# FAT42.net
KiCad netlist of a schematic drawn in Altium Designer
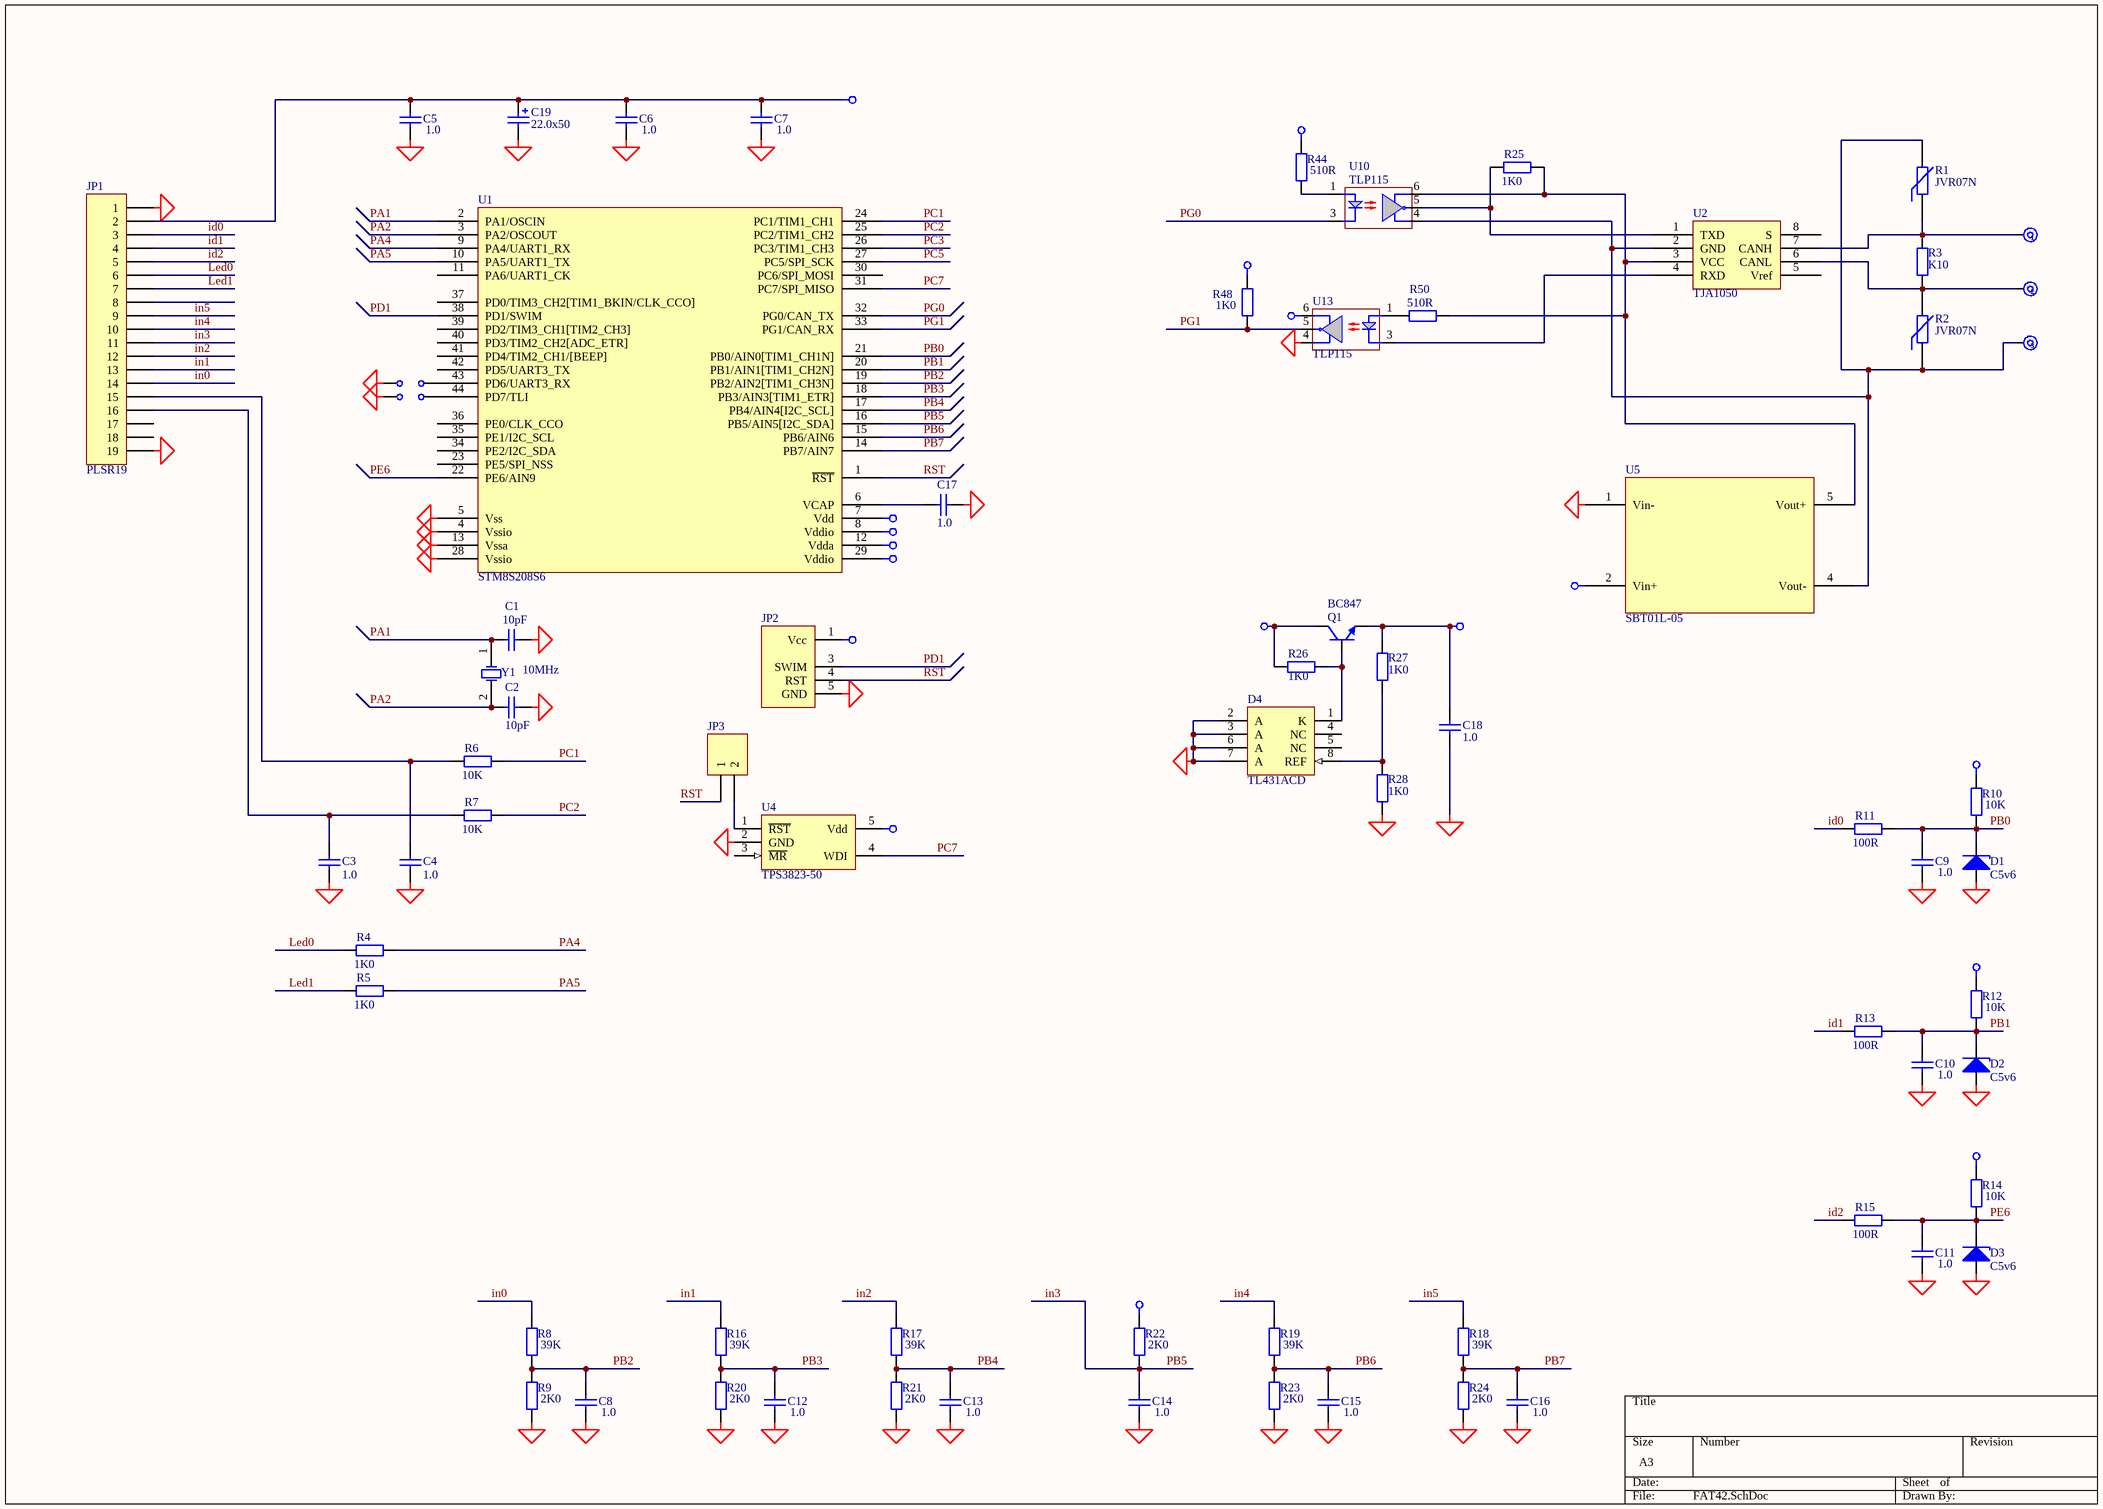
[diagram p0: FAT42.SchDoc]

(export (version "E")
  (design (tool "Eeschema 10.0.6"))
  (components
    (comp (ref "1")
      (value "~")
      (footprint "PIN2R")
      (description "Socket")
      (fields (field (name "MANUFACTURER") "Generic Components") (field (name "PUBLISHER") "Altium Limited"))
      (libsource (lib "PAL") (part "Socket_Ring"))
    )
    (comp (ref "2")
      (value "~")
      (footprint "PIN2R")
      (description "Socket")
      (fields (field (name "MANUFACTURER") "Generic Components") (field (name "PUBLISHER") "Altium Limited"))
      (libsource (lib "PAL") (part "Socket_Ring"))
    )
    (comp (ref "3")
      (value "~")
      (footprint "PIN2R")
      (description "Socket")
      (fields (field (name "MANUFACTURER") "Generic Components") (field (name "PUBLISHER") "Altium Limited"))
      (libsource (lib "PAL") (part "Socket_Ring"))
    )
    (comp (ref "C1")
      (value "10pF")
      (footprint "_1206")
      (description "Capacitor (Semiconductor SIM Model)")
      (fields (field (name "MANUFACTURER") "Generic Components") (field (name "PUBLISHER") "Altium Limited"))
      (libsource (lib "Miscellaneous Devices") (part "Cap Semi"))
    )
    (comp (ref "C2")
      (value "10pF")
      (footprint "_1206")
      (description "Capacitor (Semiconductor SIM Model)")
      (fields (field (name "MANUFACTURER") "Generic Components") (field (name "PUBLISHER") "Altium Limited"))
      (libsource (lib "Miscellaneous Devices") (part "Cap Semi"))
    )
    (comp (ref "C3")
      (value "1.0")
      (footprint "_1206")
      (description "Capacitor (Semiconductor SIM Model)")
      (fields (field (name "MANUFACTURER") "Generic Components") (field (name "PUBLISHER") "Altium Limited"))
      (libsource (lib "Miscellaneous Devices") (part "Cap Semi"))
    )
    (comp (ref "C4")
      (value "1.0")
      (footprint "_1206")
      (description "Capacitor (Semiconductor SIM Model)")
      (fields (field (name "MANUFACTURER") "Generic Components") (field (name "PUBLISHER") "Altium Limited"))
      (libsource (lib "Miscellaneous Devices") (part "Cap Semi"))
    )
    (comp (ref "C5")
      (value "1.0")
      (footprint "_1206")
      (description "Capacitor (Semiconductor SIM Model)")
      (fields (field (name "MANUFACTURER") "Generic Components") (field (name "PUBLISHER") "Altium Limited"))
      (libsource (lib "Miscellaneous Devices") (part "Cap Semi"))
    )
    (comp (ref "C6")
      (value "1.0")
      (footprint "_1206")
      (description "Capacitor (Semiconductor SIM Model)")
      (fields (field (name "MANUFACTURER") "Generic Components") (field (name "PUBLISHER") "Altium Limited"))
      (libsource (lib "Miscellaneous Devices") (part "Cap Semi"))
    )
    (comp (ref "C7")
      (value "1.0")
      (footprint "_1206")
      (description "Capacitor (Semiconductor SIM Model)")
      (fields (field (name "MANUFACTURER") "Generic Components") (field (name "PUBLISHER") "Altium Limited"))
      (libsource (lib "Miscellaneous Devices") (part "Cap Semi"))
    )
    (comp (ref "C8")
      (value "1.0")
      (footprint "_1206")
      (description "Capacitor (Semiconductor SIM Model)")
      (fields (field (name "MANUFACTURER") "Generic Components") (field (name "PUBLISHER") "Altium Limited"))
      (libsource (lib "Miscellaneous Devices") (part "Cap Semi"))
    )
    (comp (ref "C9")
      (value "1.0")
      (footprint "_1206")
      (description "Capacitor (Semiconductor SIM Model)")
      (fields (field (name "MANUFACTURER") "Generic Components") (field (name "PUBLISHER") "Altium Limited"))
      (libsource (lib "Miscellaneous Devices") (part "Cap Semi"))
    )
    (comp (ref "C10")
      (value "1.0")
      (footprint "_1206")
      (description "Capacitor (Semiconductor SIM Model)")
      (fields (field (name "MANUFACTURER") "Generic Components") (field (name "PUBLISHER") "Altium Limited"))
      (libsource (lib "Miscellaneous Devices") (part "Cap Semi"))
    )
    (comp (ref "C11")
      (value "1.0")
      (footprint "_1206")
      (description "Capacitor (Semiconductor SIM Model)")
      (fields (field (name "MANUFACTURER") "Generic Components") (field (name "PUBLISHER") "Altium Limited"))
      (libsource (lib "Miscellaneous Devices") (part "Cap Semi"))
    )
    (comp (ref "C12")
      (value "1.0")
      (footprint "_1206")
      (description "Capacitor (Semiconductor SIM Model)")
      (fields (field (name "MANUFACTURER") "Generic Components") (field (name "PUBLISHER") "Altium Limited"))
      (libsource (lib "Miscellaneous Devices") (part "Cap Semi"))
    )
    (comp (ref "C13")
      (value "1.0")
      (footprint "_1206")
      (description "Capacitor (Semiconductor SIM Model)")
      (fields (field (name "MANUFACTURER") "Generic Components") (field (name "PUBLISHER") "Altium Limited"))
      (libsource (lib "Miscellaneous Devices") (part "Cap Semi"))
    )
    (comp (ref "C14")
      (value "1.0")
      (footprint "_1206")
      (description "Capacitor (Semiconductor SIM Model)")
      (fields (field (name "MANUFACTURER") "Generic Components") (field (name "PUBLISHER") "Altium Limited"))
      (libsource (lib "Miscellaneous Devices") (part "Cap Semi"))
    )
    (comp (ref "C15")
      (value "1.0")
      (footprint "_1206")
      (description "Capacitor (Semiconductor SIM Model)")
      (fields (field (name "MANUFACTURER") "Generic Components") (field (name "PUBLISHER") "Altium Limited"))
      (libsource (lib "Miscellaneous Devices") (part "Cap Semi"))
    )
    (comp (ref "C16")
      (value "1.0")
      (footprint "_1206")
      (description "Capacitor (Semiconductor SIM Model)")
      (fields (field (name "MANUFACTURER") "Generic Components") (field (name "PUBLISHER") "Altium Limited"))
      (libsource (lib "Miscellaneous Devices") (part "Cap Semi"))
    )
    (comp (ref "C17")
      (value "1.0")
      (footprint "_1206")
      (description "Capacitor (Semiconductor SIM Model)")
      (fields (field (name "MANUFACTURER") "Generic Components") (field (name "PUBLISHER") "Altium Limited"))
      (libsource (lib "Miscellaneous Devices") (part "Cap Semi"))
    )
    (comp (ref "C18")
      (value "1.0")
      (footprint "_1206")
      (description "Capacitor (Semiconductor SIM Model)")
      (fields (field (name "MANUFACTURER") "Generic Components") (field (name "PUBLISHER") "Altium Limited"))
      (libsource (lib "Miscellaneous Devices") (part "Cap Semi"))
    )
    (comp (ref "C19")
      (value "22.0x50")
      (footprint "el3")
      (description "Polarized Capacitor (Radial)")
      (fields (field (name "MANUFACTURER") "Generic Components") (field (name "PUBLISHER") "Altium Limited"))
      (libsource (lib "PAL") (part "Cap Pol1"))
    )
    (comp (ref "D1")
      (value "C5v6")
      (footprint "_1206d")
      (description "Default Diode")
      (fields (field (name "MANUFACTURER") "Generic Components") (field (name "PUBLISHER") "Altium Limited"))
      (libsource (lib "PAL") (part "Zener"))
    )
    (comp (ref "D2")
      (value "C5v6")
      (footprint "_1206d")
      (description "Default Diode")
      (fields (field (name "MANUFACTURER") "Generic Components") (field (name "PUBLISHER") "Altium Limited"))
      (libsource (lib "PAL") (part "Zener"))
    )
    (comp (ref "D3")
      (value "C5v6")
      (footprint "_1206d")
      (description "Default Diode")
      (fields (field (name "MANUFACTURER") "Generic Components") (field (name "PUBLISHER") "Altium Limited"))
      (libsource (lib "PAL") (part "Zener"))
    )
    (comp (ref "D4")
      (value "TL431ACD")
      (footprint "SO-G8")
      (description "Programmable Precision Reference")
      (fields (field (name "MANUFACTURER") "Motorola") (field (name "PUBLISHER") "Altium Limited"))
      (libsource (lib "Motorola Power Management Voltage Reference") (part "TL431ACD"))
    )
    (comp (ref "J1")
      (value "~")
      (footprint "jmp")
      (description "Switch")
      (fields (field (name "MANUFACTURER") "Generic Components") (field (name "PUBLISHER") "Altium Limited"))
      (libsource (lib "PAL") (part "JMP"))
    )
    (comp (ref "J2")
      (value "~")
      (footprint "jmp")
      (description "Switch")
      (fields (field (name "MANUFACTURER") "Generic Components") (field (name "PUBLISHER") "Altium Limited"))
      (libsource (lib "PAL") (part "JMP"))
    )
    (comp (ref "JP1")
      (value "PLSR19")
      (footprint "HDR1X19")
      (description "Header, 19-Pin")
      (fields (field (name "MANUFACTURER") "Generic Components") (field (name "PUBLISHER") "Altium Limited"))
      (libsource (lib "Miscellaneous Connectors") (part "Header 19"))
    )
    (comp (ref "JP2") (value "~") (footprint "HDR1X5_uart") (libsource (lib "PAL") (part "SWIM_CONN")))
    (comp (ref "JP3")
      (value "PLS2")
      (footprint "HDR1X2")
      (description "Header, 2-Pin")
      (fields (field (name "MANUFACTURER") "Generic Components") (field (name "PUBLISHER") "Altium Limited"))
      (libsource (lib "Miscellaneous Connectors") (part "Header 2"))
    )
    (comp (ref "Q1")
      (value "BC847")
      (footprint "SO-G3")
      (description "General Purpose Transistor NPN Silicon")
      (fields (field (name "MANUFACTURER") "Motorola") (field (name "PUBLISHER") "Altium Limited"))
      (libsource (lib "PAL") (part "BC847ALT1"))
    )
    (comp (ref "R1")
      (value "JVR07N")
      (footprint "JVR07N")
      (description "Varistor (Voltage-Sensitive Resistor)")
      (fields (field (name "MANUFACTURER") "Generic Components") (field (name "PUBLISHER") "Altium Limited"))
      (libsource (lib "Miscellaneous Devices") (part "Res Varistor"))
    )
    (comp (ref "R2")
      (value "JVR07N")
      (footprint "JVR07N")
      (description "Varistor (Voltage-Sensitive Resistor)")
      (fields (field (name "MANUFACTURER") "Generic Components") (field (name "PUBLISHER") "Altium Limited"))
      (libsource (lib "Miscellaneous Devices") (part "Res Varistor"))
    )
    (comp (ref "R3")
      (value "K10")
      (footprint "_1206")
      (description "Resistor")
      (fields (field (name "MANUFACTURER") "Generic Components") (field (name "PUBLISHER") "Altium Limited"))
      (libsource (lib "") (part "Res2_3"))
    )
    (comp (ref "R4")
      (value "1K0")
      (footprint "_1206")
      (description "Resistor")
      (fields (field (name "MANUFACTURER") "Generic Components") (field (name "PUBLISHER") "Altium Limited"))
      (libsource (lib "") (part "Res2_3"))
    )
    (comp (ref "R5")
      (value "1K0")
      (footprint "_1206")
      (description "Resistor")
      (fields (field (name "MANUFACTURER") "Generic Components") (field (name "PUBLISHER") "Altium Limited"))
      (libsource (lib "") (part "Res2_3"))
    )
    (comp (ref "R6")
      (value "10K")
      (footprint "_1206")
      (description "Resistor")
      (fields (field (name "MANUFACTURER") "Generic Components") (field (name "PUBLISHER") "Altium Limited"))
      (libsource (lib "") (part "Res2_2"))
    )
    (comp (ref "R7")
      (value "10K")
      (footprint "_1206")
      (description "Resistor")
      (fields (field (name "MANUFACTURER") "Generic Components") (field (name "PUBLISHER") "Altium Limited"))
      (libsource (lib "") (part "Res2_2"))
    )
    (comp (ref "R8")
      (value "39K")
      (footprint "_1206")
      (description "Resistor")
      (fields (field (name "MANUFACTURER") "Generic Components") (field (name "PUBLISHER") "Altium Limited"))
      (libsource (lib "Miscellaneous Devices") (part "Res2"))
    )
    (comp (ref "R9")
      (value "2K0")
      (footprint "_1206")
      (description "Resistor")
      (fields (field (name "MANUFACTURER") "Generic Components") (field (name "PUBLISHER") "Altium Limited"))
      (libsource (lib "Miscellaneous Devices") (part "Res2"))
    )
    (comp (ref "R10")
      (value "10K")
      (footprint "_1206")
      (description "Resistor")
      (fields (field (name "MANUFACTURER") "Generic Components") (field (name "PUBLISHER") "Altium Limited"))
      (libsource (lib "") (part "Res2_1"))
    )
    (comp (ref "R11")
      (value "100R")
      (footprint "_1206")
      (description "Resistor")
      (fields (field (name "MANUFACTURER") "Generic Components") (field (name "PUBLISHER") "Altium Limited"))
      (libsource (lib "") (part "Res2_2"))
    )
    (comp (ref "R12")
      (value "10K")
      (footprint "_1206")
      (description "Resistor")
      (fields (field (name "MANUFACTURER") "Generic Components") (field (name "PUBLISHER") "Altium Limited"))
      (libsource (lib "") (part "Res2_1"))
    )
    (comp (ref "R13")
      (value "100R")
      (footprint "_1206")
      (description "Resistor")
      (fields (field (name "MANUFACTURER") "Generic Components") (field (name "PUBLISHER") "Altium Limited"))
      (libsource (lib "") (part "Res2_2"))
    )
    (comp (ref "R14")
      (value "10K")
      (footprint "_1206")
      (description "Resistor")
      (fields (field (name "MANUFACTURER") "Generic Components") (field (name "PUBLISHER") "Altium Limited"))
      (libsource (lib "") (part "Res2_1"))
    )
    (comp (ref "R15")
      (value "100R")
      (footprint "_1206")
      (description "Resistor")
      (fields (field (name "MANUFACTURER") "Generic Components") (field (name "PUBLISHER") "Altium Limited"))
      (libsource (lib "") (part "Res2_2"))
    )
    (comp (ref "R16")
      (value "39K")
      (footprint "_1206")
      (description "Resistor")
      (fields (field (name "MANUFACTURER") "Generic Components") (field (name "PUBLISHER") "Altium Limited"))
      (libsource (lib "Miscellaneous Devices") (part "Res2"))
    )
    (comp (ref "R17")
      (value "39K")
      (footprint "_1206")
      (description "Resistor")
      (fields (field (name "MANUFACTURER") "Generic Components") (field (name "PUBLISHER") "Altium Limited"))
      (libsource (lib "Miscellaneous Devices") (part "Res2"))
    )
    (comp (ref "R18")
      (value "39K")
      (footprint "_1206")
      (description "Resistor")
      (fields (field (name "MANUFACTURER") "Generic Components") (field (name "PUBLISHER") "Altium Limited"))
      (libsource (lib "Miscellaneous Devices") (part "Res2"))
    )
    (comp (ref "R19")
      (value "39K")
      (footprint "_1206")
      (description "Resistor")
      (fields (field (name "MANUFACTURER") "Generic Components") (field (name "PUBLISHER") "Altium Limited"))
      (libsource (lib "Miscellaneous Devices") (part "Res2"))
    )
    (comp (ref "R20")
      (value "2K0")
      (footprint "_1206")
      (description "Resistor")
      (fields (field (name "MANUFACTURER") "Generic Components") (field (name "PUBLISHER") "Altium Limited"))
      (libsource (lib "Miscellaneous Devices") (part "Res2"))
    )
    (comp (ref "R21")
      (value "2K0")
      (footprint "_1206")
      (description "Resistor")
      (fields (field (name "MANUFACTURER") "Generic Components") (field (name "PUBLISHER") "Altium Limited"))
      (libsource (lib "Miscellaneous Devices") (part "Res2"))
    )
    (comp (ref "R22")
      (value "2K0")
      (footprint "_1206")
      (description "Resistor")
      (fields (field (name "MANUFACTURER") "Generic Components") (field (name "PUBLISHER") "Altium Limited"))
      (libsource (lib "Miscellaneous Devices") (part "Res2"))
    )
    (comp (ref "R23")
      (value "2K0")
      (footprint "_1206")
      (description "Resistor")
      (fields (field (name "MANUFACTURER") "Generic Components") (field (name "PUBLISHER") "Altium Limited"))
      (libsource (lib "Miscellaneous Devices") (part "Res2"))
    )
    (comp (ref "R24")
      (value "2K0")
      (footprint "_1206")
      (description "Resistor")
      (fields (field (name "MANUFACTURER") "Generic Components") (field (name "PUBLISHER") "Altium Limited"))
      (libsource (lib "Miscellaneous Devices") (part "Res2"))
    )
    (comp (ref "R25")
      (value "1K0")
      (footprint "_1206")
      (description "Resistor")
      (fields (field (name "MANUFACTURER") "Generic Components") (field (name "PUBLISHER") "Altium Limited"))
      (libsource (lib "") (part "Res2_5"))
    )
    (comp (ref "R26")
      (value "1K0")
      (footprint "_1206")
      (description "Resistor")
      (fields (field (name "MANUFACTURER") "Generic Components") (field (name "PUBLISHER") "Altium Limited"))
      (libsource (lib "") (part "Res2_5"))
    )
    (comp (ref "R27")
      (value "1K0")
      (footprint "_1206")
      (description "Resistor")
      (fields (field (name "MANUFACTURER") "Generic Components") (field (name "PUBLISHER") "Altium Limited"))
      (libsource (lib "") (part "Res2_3"))
    )
    (comp (ref "R28")
      (value "1K0")
      (footprint "_1206")
      (description "Resistor")
      (fields (field (name "MANUFACTURER") "Generic Components") (field (name "PUBLISHER") "Altium Limited"))
      (libsource (lib "") (part "Res2_3"))
    )
    (comp (ref "R44")
      (value "510R")
      (footprint "_1206")
      (description "Resistor")
      (fields (field (name "MANUFACTURER") "Generic Components") (field (name "PUBLISHER") "Altium Limited"))
      (libsource (lib "") (part "Res2_3"))
    )
    (comp (ref "R48")
      (value "1K0")
      (footprint "_1206")
      (description "Resistor")
      (fields (field (name "MANUFACTURER") "Generic Components") (field (name "PUBLISHER") "Altium Limited"))
      (libsource (lib "") (part "Res2_3"))
    )
    (comp (ref "R50")
      (value "510R")
      (footprint "_1206")
      (description "Resistor")
      (fields (field (name "MANUFACTURER") "Generic Components") (field (name "PUBLISHER") "Altium Limited"))
      (libsource (lib "") (part "Res2_4"))
    )
    (comp (ref "U1")
      (value "STM8S208S6")
      (footprint "QFP10X10-G44/G10N")
      (libsource (lib "PAL") (part "STM8S208S6"))
    )
    (comp (ref "U2") (value "TJA1050") (footprint "SO-G8/D5") (libsource (lib "PAL") (part "TJA1050")))
    (comp (ref "U4")
      (value "TPS3823-50")
      (footprint "SO-G5/P.95")
      (description "Reset IC")
      (fields
        (field (name "MANUFACTURER") "National Semiconductor")
        (field (name "PUBLISHER") "Altium Limited")
      )
      (libsource (lib "PAL") (part "TPS3823"))
    )
    (comp (ref "U5") (value "SBT01L-05") (footprint "SBT01DET01") (libsource (lib "PAL") (part "SBT01L")))
    (comp (ref "U10") (value "TLP115") (footprint "tlp115") (libsource (lib "") (part "TLP115_1")))
    (comp (ref "U13") (value "TLP115") (footprint "tlp115") (libsource (lib "PAL") (part "TLP115")))
    (comp (ref "Y1")
      (value "10MHz")
      (footprint "QWARZ1")
      (description "Crystal Oscillator")
      (fields (field (name "MANUFACTURER") "Generic Components") (field (name "PUBLISHER") "Altium Limited"))
      (libsource (lib "Miscellaneous Devices") (part "XTAL"))
    )
  )
  (nets
    (net (code "1") (name "+5v") (class "Default")
      (node (ref "C19") (pin "1") (pinfunction "1_1") (pintype "passive"))
      (node (ref "C5") (pin "2") (pinfunction "2_2") (pintype "passive"))
      (node (ref "C6") (pin "2") (pinfunction "2_2") (pintype "passive"))
      (node (ref "C7") (pin "2") (pinfunction "2_2") (pintype "passive"))
      (node (ref "JP1") (pin "2") (pinfunction "2_2") (pintype "passive"))
      (node (ref "JP2") (pin "1") (pinfunction "Vcc_1") (pintype "passive"))
      (node (ref "Q1") (pin "3") (pinfunction "C_3") (pintype "passive"))
      (node (ref "R10") (pin "1") (pinfunction "1_1") (pintype "passive"))
      (node (ref "R12") (pin "1") (pinfunction "1_1") (pintype "passive"))
      (node (ref "R14") (pin "1") (pinfunction "1_1") (pintype "passive"))
      (node (ref "R22") (pin "2") (pinfunction "2_2") (pintype "passive"))
      (node (ref "R26") (pin "1") (pinfunction "1_1") (pintype "passive"))
      (node (ref "R44") (pin "2") (pinfunction "2_2") (pintype "passive"))
      (node (ref "R48") (pin "2") (pinfunction "2_2") (pintype "passive"))
      (node (ref "U1") (pin "29") (pinfunction "Vddio_29") (pintype "passive"))
      (node (ref "U1") (pin "7") (pinfunction "Vdd_7") (pintype "passive"))
      (node (ref "U1") (pin "8") (pinfunction "Vddio_8") (pintype "passive"))
      (node (ref "U13") (pin "6") (pinfunction "6_6") (pintype "passive"))
      (node (ref "U4") (pin "5") (pinfunction "Vdd_5") (pintype "power_in"))
      (node (ref "U5") (pin "2") (pinfunction "Vin+_2") (pintype "passive"))
    )
    (net (code "2") (name "/Led0") (class "Default")
      (node (ref "JP1") (pin "6") (pinfunction "6_6") (pintype "passive"))
      (node (ref "R4") (pin "1") (pinfunction "1_1") (pintype "passive"))
    )
    (net (code "3") (name "/Led1") (class "Default")
      (node (ref "JP1") (pin "7") (pinfunction "7_7") (pintype "passive"))
      (node (ref "R5") (pin "1") (pinfunction "1_1") (pintype "passive"))
    )
    (net (code "4") (name "/PA1") (class "Default")
      (node (ref "C1") (pin "2") (pinfunction "2_2") (pintype "passive"))
      (node (ref "U1") (pin "2") (pinfunction "PA1/OSCIN_2") (pintype "passive"))
      (node (ref "Y1") (pin "1") (pinfunction "OSC1_1") (pintype "passive"))
    )
    (net (code "5") (name "/PA2") (class "Default")
      (node (ref "C2") (pin "2") (pinfunction "2_2") (pintype "passive"))
      (node (ref "U1") (pin "3") (pinfunction "PA2/OSCOUT_3") (pintype "passive"))
      (node (ref "Y1") (pin "2") (pinfunction "OSC2_2") (pintype "passive"))
    )
    (net (code "6") (name "/PA4") (class "Default")
      (node (ref "R4") (pin "2") (pinfunction "2_2") (pintype "passive"))
      (node (ref "U1") (pin "9") (pinfunction "PA4/UART1_RX_9") (pintype "passive"))
    )
    (net (code "7") (name "/PA5") (class "Default")
      (node (ref "R5") (pin "2") (pinfunction "2_2") (pintype "passive"))
      (node (ref "U1") (pin "10") (pinfunction "PA5/UART1_TX_10") (pintype "passive"))
    )
    (net (code "8") (name "/PB0") (class "Default")
      (node (ref "C9") (pin "2") (pinfunction "2_2") (pintype "passive"))
      (node (ref "D1") (pin "2") (pinfunction "K_2") (pintype "passive"))
      (node (ref "R10") (pin "2") (pinfunction "2_2") (pintype "passive"))
      (node (ref "R11") (pin "1") (pinfunction "1_1") (pintype "passive"))
      (node (ref "U1") (pin "21") (pinfunction "PB0/AIN0[TIM1_CH1N]_21") (pintype "passive"))
    )
    (net (code "9") (name "/PB1") (class "Default")
      (node (ref "C10") (pin "2") (pinfunction "2_2") (pintype "passive"))
      (node (ref "D2") (pin "2") (pinfunction "K_2") (pintype "passive"))
      (node (ref "R12") (pin "2") (pinfunction "2_2") (pintype "passive"))
      (node (ref "R13") (pin "1") (pinfunction "1_1") (pintype "passive"))
      (node (ref "U1") (pin "20") (pinfunction "PB1/AIN1[TIM1_CH2N]_20") (pintype "passive"))
    )
    (net (code "10") (name "/PB2") (class "Default")
      (node (ref "C8") (pin "2") (pinfunction "2_2") (pintype "passive"))
      (node (ref "R8") (pin "1") (pinfunction "1_1") (pintype "passive"))
      (node (ref "R9") (pin "2") (pinfunction "2_2") (pintype "passive"))
      (node (ref "U1") (pin "19") (pinfunction "PB2/AIN2[TIM1_CH3N]_19") (pintype "passive"))
    )
    (net (code "11") (name "/PB3") (class "Default")
      (node (ref "C12") (pin "2") (pinfunction "2_2") (pintype "passive"))
      (node (ref "R16") (pin "1") (pinfunction "1_1") (pintype "passive"))
      (node (ref "R20") (pin "2") (pinfunction "2_2") (pintype "passive"))
      (node (ref "U1") (pin "18") (pinfunction "PB3/AIN3[TIM1_ETR]_18") (pintype "passive"))
    )
    (net (code "12") (name "/PB4") (class "Default")
      (node (ref "C13") (pin "2") (pinfunction "2_2") (pintype "passive"))
      (node (ref "R17") (pin "1") (pinfunction "1_1") (pintype "passive"))
      (node (ref "R21") (pin "2") (pinfunction "2_2") (pintype "passive"))
      (node (ref "U1") (pin "17") (pinfunction "PB4/AIN4[I2C_SCL]_17") (pintype "passive"))
    )
    (net (code "13") (name "/PB5") (class "Default")
      (node (ref "C14") (pin "2") (pinfunction "2_2") (pintype "passive"))
      (node (ref "JP1") (pin "11") (pinfunction "11_11") (pintype "passive"))
      (node (ref "R22") (pin "1") (pinfunction "1_1") (pintype "passive"))
      (node (ref "U1") (pin "16") (pinfunction "PB5/AIN5[I2C_SDA]_16") (pintype "passive"))
    )
    (net (code "14") (name "/PB6") (class "Default")
      (node (ref "C15") (pin "2") (pinfunction "2_2") (pintype "passive"))
      (node (ref "R19") (pin "1") (pinfunction "1_1") (pintype "passive"))
      (node (ref "R23") (pin "2") (pinfunction "2_2") (pintype "passive"))
      (node (ref "U1") (pin "15") (pinfunction "PB6/AIN6_15") (pintype "passive"))
    )
    (net (code "15") (name "/PB7") (class "Default")
      (node (ref "C16") (pin "2") (pinfunction "2_2") (pintype "passive"))
      (node (ref "R18") (pin "1") (pinfunction "1_1") (pintype "passive"))
      (node (ref "R24") (pin "2") (pinfunction "2_2") (pintype "passive"))
      (node (ref "U1") (pin "14") (pinfunction "PB7/AIN7_14") (pintype "passive"))
    )
    (net (code "16") (name "/PC1") (class "Default")
      (node (ref "R6") (pin "1") (pinfunction "1_1") (pintype "passive"))
      (node (ref "U1") (pin "24") (pinfunction "PC1/TIM1_CH1_24") (pintype "passive"))
    )
    (net (code "17") (name "/PC2") (class "Default")
      (node (ref "R7") (pin "1") (pinfunction "1_1") (pintype "passive"))
      (node (ref "U1") (pin "25") (pinfunction "PC2/TIM1_CH2_25") (pintype "passive"))
    )
    (net (code "18") (name "/PC3") (class "Default")
      (node (ref "U1") (pin "26") (pinfunction "PC3/TIM1_CH3_26") (pintype "passive"))
    )
    (net (code "19") (name "/PC5") (class "Default")
      (node (ref "U1") (pin "27") (pinfunction "PC5/SPI_SCK_27") (pintype "passive"))
    )
    (net (code "20") (name "/PC7") (class "Default")
      (node (ref "U1") (pin "31") (pinfunction "PC7/SPI_MISO_31") (pintype "passive"))
      (node (ref "U4") (pin "4") (pinfunction "WDI_4") (pintype "passive"))
    )
    (net (code "21") (name "/PD1") (class "Default")
      (node (ref "JP2") (pin "3") (pinfunction "SWIM_3") (pintype "passive"))
      (node (ref "U1") (pin "38") (pinfunction "PD1/SWIM_38") (pintype "passive"))
    )
    (net (code "22") (name "/PE6") (class "Default")
      (node (ref "C11") (pin "2") (pinfunction "2_2") (pintype "passive"))
      (node (ref "D3") (pin "2") (pinfunction "K_2") (pintype "passive"))
      (node (ref "R14") (pin "2") (pinfunction "2_2") (pintype "passive"))
      (node (ref "R15") (pin "1") (pinfunction "1_1") (pintype "passive"))
      (node (ref "U1") (pin "22") (pinfunction "PE6/AIN9_22") (pintype "passive"))
    )
    (net (code "23") (name "/PG0") (class "Default")
      (node (ref "U1") (pin "32") (pinfunction "PG0/CAN_TX_32") (pintype "passive"))
      (node (ref "U10") (pin "3") (pinfunction "3_3") (pintype "passive"))
    )
    (net (code "24") (name "/PG1") (class "Default")
      (node (ref "R48") (pin "1") (pinfunction "1_1") (pintype "passive"))
      (node (ref "U1") (pin "33") (pinfunction "PG1/CAN_RX_33") (pintype "passive"))
      (node (ref "U13") (pin "5") (pinfunction "5_5") (pintype "passive"))
    )
    (net (code "25") (name "/RST") (class "Default")
      (node (ref "JP2") (pin "4") (pinfunction "RST_4") (pintype "passive"))
      (node (ref "JP3") (pin "1") (pinfunction "1_1") (pintype "passive"))
      (node (ref "U1") (pin "1") (pinfunction "~{RST}_1") (pintype "passive"))
    )
    (net (code "26") (name "/id0") (class "Default")
      (node (ref "JP1") (pin "3") (pinfunction "3_3") (pintype "passive"))
      (node (ref "R11") (pin "2") (pinfunction "2_2") (pintype "passive"))
    )
    (net (code "27") (name "/id1") (class "Default")
      (node (ref "JP1") (pin "4") (pinfunction "4_4") (pintype "passive"))
      (node (ref "R13") (pin "2") (pinfunction "2_2") (pintype "passive"))
    )
    (net (code "28") (name "/id2") (class "Default")
      (node (ref "JP1") (pin "5") (pinfunction "5_5") (pintype "passive"))
      (node (ref "R15") (pin "2") (pinfunction "2_2") (pintype "passive"))
    )
    (net (code "29") (name "/in0") (class "Default")
      (node (ref "JP1") (pin "14") (pinfunction "14_14") (pintype "passive"))
      (node (ref "R8") (pin "2") (pinfunction "2_2") (pintype "passive"))
    )
    (net (code "30") (name "/in1") (class "Default")
      (node (ref "JP1") (pin "13") (pinfunction "13_13") (pintype "passive"))
      (node (ref "R16") (pin "2") (pinfunction "2_2") (pintype "passive"))
    )
    (net (code "31") (name "/in2") (class "Default")
      (node (ref "JP1") (pin "12") (pinfunction "12_12") (pintype "passive"))
      (node (ref "R17") (pin "2") (pinfunction "2_2") (pintype "passive"))
    )
    (net (code "32") (name "/in4") (class "Default")
      (node (ref "JP1") (pin "10") (pinfunction "10_10") (pintype "passive"))
      (node (ref "R19") (pin "2") (pinfunction "2_2") (pintype "passive"))
    )
    (net (code "33") (name "/in5") (class "Default")
      (node (ref "JP1") (pin "9") (pinfunction "9_9") (pintype "passive"))
      (node (ref "R18") (pin "2") (pinfunction "2_2") (pintype "passive"))
    )
    (net (code "34") (name "GND") (class "Default")
      (node (ref "C1") (pin "1") (pinfunction "1_1") (pintype "passive"))
      (node (ref "C10") (pin "1") (pinfunction "1_1") (pintype "passive"))
      (node (ref "C11") (pin "1") (pinfunction "1_1") (pintype "passive"))
      (node (ref "C12") (pin "1") (pinfunction "1_1") (pintype "passive"))
      (node (ref "C13") (pin "1") (pinfunction "1_1") (pintype "passive"))
      (node (ref "C14") (pin "1") (pinfunction "1_1") (pintype "passive"))
      (node (ref "C15") (pin "1") (pinfunction "1_1") (pintype "passive"))
      (node (ref "C16") (pin "1") (pinfunction "1_1") (pintype "passive"))
      (node (ref "C17") (pin "1") (pinfunction "1_1") (pintype "passive"))
      (node (ref "C18") (pin "1") (pinfunction "1_1") (pintype "passive"))
      (node (ref "C19") (pin "2") (pinfunction "2_2") (pintype "passive"))
      (node (ref "C2") (pin "1") (pinfunction "1_1") (pintype "passive"))
      (node (ref "C3") (pin "1") (pinfunction "1_1") (pintype "passive"))
      (node (ref "C4") (pin "1") (pinfunction "1_1") (pintype "passive"))
      (node (ref "C5") (pin "1") (pinfunction "1_1") (pintype "passive"))
      (node (ref "C6") (pin "1") (pinfunction "1_1") (pintype "passive"))
      (node (ref "C7") (pin "1") (pinfunction "1_1") (pintype "passive"))
      (node (ref "C8") (pin "1") (pinfunction "1_1") (pintype "passive"))
      (node (ref "C9") (pin "1") (pinfunction "1_1") (pintype "passive"))
      (node (ref "D1") (pin "1") (pinfunction "A_1") (pintype "passive"))
      (node (ref "D2") (pin "1") (pinfunction "A_1") (pintype "passive"))
      (node (ref "D3") (pin "1") (pinfunction "A_1") (pintype "passive"))
      (node (ref "D4") (pin "2") (pinfunction "A_2") (pintype "passive"))
      (node (ref "D4") (pin "3") (pinfunction "A_3") (pintype "passive"))
      (node (ref "D4") (pin "6") (pinfunction "A_6") (pintype "passive"))
      (node (ref "D4") (pin "7") (pinfunction "A_7") (pintype "passive"))
      (node (ref "J1") (pin "1") (pinfunction "1_1") (pintype "passive"))
      (node (ref "J2") (pin "1") (pinfunction "1_1") (pintype "passive"))
      (node (ref "JP1") (pin "1") (pinfunction "1_1") (pintype "passive"))
      (node (ref "JP1") (pin "19") (pinfunction "19_19") (pintype "passive"))
      (node (ref "JP2") (pin "5") (pinfunction "GND_5") (pintype "passive"))
      (node (ref "R20") (pin "1") (pinfunction "1_1") (pintype "passive"))
      (node (ref "R21") (pin "1") (pinfunction "1_1") (pintype "passive"))
      (node (ref "R23") (pin "1") (pinfunction "1_1") (pintype "passive"))
      (node (ref "R24") (pin "1") (pinfunction "1_1") (pintype "passive"))
      (node (ref "R28") (pin "1") (pinfunction "1_1") (pintype "passive"))
      (node (ref "R9") (pin "1") (pinfunction "1_1") (pintype "passive"))
      (node (ref "U1") (pin "13") (pinfunction "Vssa_13") (pintype "passive"))
      (node (ref "U1") (pin "28") (pinfunction "Vssio_28") (pintype "passive"))
      (node (ref "U1") (pin "4") (pinfunction "Vssio_4") (pintype "passive"))
      (node (ref "U1") (pin "5") (pinfunction "Vss_5") (pintype "passive"))
      (node (ref "U13") (pin "4") (pinfunction "4_4") (pintype "passive"))
      (node (ref "U4") (pin "2") (pinfunction "GND_2") (pintype "power_in"))
      (node (ref "U5") (pin "1") (pinfunction "Vin-_1") (pintype "passive"))
    )
    (net (code "35") (name "Net-(C3-Pad2)") (class "Default")
      (node (ref "C3") (pin "2") (pinfunction "2_2") (pintype "passive"))
      (node (ref "JP1") (pin "16") (pinfunction "16_16") (pintype "passive"))
      (node (ref "R7") (pin "2") (pinfunction "2_2") (pintype "passive"))
    )
    (net (code "36") (name "Net-(C4-Pad2)") (class "Default")
      (node (ref "C4") (pin "2") (pinfunction "2_2") (pintype "passive"))
      (node (ref "JP1") (pin "15") (pinfunction "15_15") (pintype "passive"))
      (node (ref "R6") (pin "2") (pinfunction "2_2") (pintype "passive"))
    )
    (net (code "37") (name "Net-(D4-K)") (class "Default")
      (node (ref "D4") (pin "1") (pinfunction "K_1") (pintype "passive"))
      (node (ref "Q1") (pin "1") (pinfunction "B_1") (pintype "passive"))
      (node (ref "R26") (pin "2") (pinfunction "2_2") (pintype "passive"))
    )
    (net (code "38") (name "Net-(D4-REF)") (class "Default")
      (node (ref "D4") (pin "8") (pinfunction "REF_8") (pintype "input"))
      (node (ref "R27") (pin "1") (pinfunction "1_1") (pintype "passive"))
      (node (ref "R28") (pin "2") (pinfunction "2_2") (pintype "passive"))
    )
    (net (code "39") (name "Net-(R44-Pad1)") (class "Default")
      (node (ref "R44") (pin "1") (pinfunction "1_1") (pintype "passive"))
      (node (ref "U10") (pin "1") (pinfunction "1_1") (pintype "passive"))
    )
    (net (code "40") (name "Net-(R50-Pad2)") (class "Default")
      (node (ref "R50") (pin "2") (pinfunction "2_2") (pintype "passive"))
      (node (ref "U13") (pin "1") (pinfunction "1_1") (pintype "passive"))
    )
    (net (code "41") (name "Net-(U1-PD6{slash}UART3_RX)") (class "Default")
      (node (ref "J1") (pin "2") (pinfunction "2_2") (pintype "passive"))
      (node (ref "U1") (pin "43") (pinfunction "PD6/UART3_RX_43") (pintype "passive"))
    )
    (net (code "42") (name "Net-(U1-PD7{slash}TLI)") (class "Default")
      (node (ref "J2") (pin "2") (pinfunction "2_2") (pintype "passive"))
      (node (ref "U1") (pin "44") (pinfunction "PD7/TLI_44") (pintype "passive"))
    )
    (net (code "43") (name "Net-(U1-VCAP)") (class "Default")
      (node (ref "C17") (pin "2") (pinfunction "2_2") (pintype "passive"))
      (node (ref "U1") (pin "6") (pinfunction "VCAP_6") (pintype "passive"))
    )
    (net (code "44") (name "Net-(U2-CANH)") (class "Default")
      (node (ref "1") (pin "1") (pinfunction "1_1") (pintype "passive"))
      (node (ref "R1") (pin "1") (pinfunction "1_1") (pintype "passive"))
      (node (ref "R3") (pin "2") (pinfunction "2_2") (pintype "passive"))
      (node (ref "U2") (pin "7") (pinfunction "CANH_7") (pintype "passive"))
    )
    (net (code "45") (name "Net-(U2-CANL)") (class "Default")
      (node (ref "2") (pin "1") (pinfunction "1_1") (pintype "passive"))
      (node (ref "R2") (pin "2") (pinfunction "2_2") (pintype "passive"))
      (node (ref "R3") (pin "1") (pinfunction "1_1") (pintype "passive"))
      (node (ref "U2") (pin "6") (pinfunction "CANL_6") (pintype "passive"))
    )
    (net (code "46") (name "Net-(U2-GND)") (class "Default")
      (node (ref "3") (pin "1") (pinfunction "1_1") (pintype "passive"))
      (node (ref "R1") (pin "2") (pinfunction "2_2") (pintype "passive"))
      (node (ref "R2") (pin "1") (pinfunction "1_1") (pintype "passive"))
      (node (ref "U10") (pin "4") (pinfunction "4_4") (pintype "passive"))
      (node (ref "U2") (pin "2") (pinfunction "GND_2") (pintype "passive"))
      (node (ref "U5") (pin "4") (pinfunction "Vout-_4") (pintype "passive"))
    )
    (net (code "47") (name "Net-(U2-RXD)") (class "Default")
      (node (ref "U13") (pin "3") (pinfunction "3_3") (pintype "passive"))
      (node (ref "U2") (pin "4") (pinfunction "RXD_4") (pintype "passive"))
    )
    (net (code "48") (name "Net-(U2-TXD)") (class "Default")
      (node (ref "R25") (pin "1") (pinfunction "1_1") (pintype "passive"))
      (node (ref "U10") (pin "5") (pinfunction "5_5") (pintype "passive"))
      (node (ref "U2") (pin "1") (pinfunction "TXD_1") (pintype "passive"))
    )
    (net (code "49") (name "Net-(U2-VCC)") (class "Default")
      (node (ref "R25") (pin "2") (pinfunction "2_2") (pintype "passive"))
      (node (ref "R50") (pin "1") (pinfunction "1_1") (pintype "passive"))
      (node (ref "U10") (pin "6") (pinfunction "6_6") (pintype "passive"))
      (node (ref "U2") (pin "3") (pinfunction "VCC_3") (pintype "passive"))
      (node (ref "U5") (pin "5") (pinfunction "Vout+_5") (pintype "passive"))
    )
    (net (code "50") (name "Net-(U4-~{RST})") (class "Default")
      (node (ref "JP3") (pin "2") (pinfunction "2_2") (pintype "passive"))
      (node (ref "U4") (pin "1") (pinfunction "~{RST}_1") (pintype "power_in"))
    )
    (net (code "51") (name "Uref") (class "Default")
      (node (ref "C18") (pin "2") (pinfunction "2_2") (pintype "passive"))
      (node (ref "Q1") (pin "2") (pinfunction "E_2") (pintype "passive"))
      (node (ref "R27") (pin "2") (pinfunction "2_2") (pintype "passive"))
      (node (ref "U1") (pin "12") (pinfunction "Vdda_12") (pintype "passive"))
    )
    (net (code "52") (name "unconnected-(D4-NC-Pad4)") (class "Default")
      (node (ref "D4") (pin "4") (pinfunction "NC_4") (pintype "passive"))
    )
    (net (code "53") (name "unconnected-(D4-NC-Pad5)") (class "Default")
      (node (ref "D4") (pin "5") (pinfunction "NC_5") (pintype "passive"))
    )
    (net (code "54") (name "unconnected-(JP1-Pad8)") (class "Default")
      (node (ref "JP1") (pin "8") (pinfunction "8_8") (pintype "passive"))
    )
    (net (code "55") (name "unconnected-(JP1-Pad17)") (class "Default")
      (node (ref "JP1") (pin "17") (pinfunction "17_17") (pintype "passive"))
    )
    (net (code "56") (name "unconnected-(JP1-Pad18)") (class "Default")
      (node (ref "JP1") (pin "18") (pinfunction "18_18") (pintype "passive"))
    )
    (net (code "57") (name "unconnected-(U1-PA6{slash}UART1_CK-Pad11)") (class "Default")
      (node (ref "U1") (pin "11") (pinfunction "PA6/UART1_CK_11") (pintype "passive"))
    )
    (net (code "58") (name "unconnected-(U1-PC6{slash}SPI_MOSI-Pad30)") (class "Default")
      (node (ref "U1") (pin "30") (pinfunction "PC6/SPI_MOSI_30") (pintype "passive"))
    )
    (net (code "59") (name "unconnected-(U1-PD0{slash}TIM3_CH2[TIM1_BKIN{slash}CLK_CCO]-Pad37)") (class "Default")
      (node (ref "U1") (pin "37") (pinfunction "PD0/TIM3_CH2[TIM1_BKIN/CLK_CCO]_37") (pintype "passive"))
    )
    (net (code "60") (name "unconnected-(U1-PD2{slash}TIM3_CH1[TIM2_CH3]-Pad39)") (class "Default")
      (node (ref "U1") (pin "39") (pinfunction "PD2/TIM3_CH1[TIM2_CH3]_39") (pintype "passive"))
    )
    (net (code "61") (name "unconnected-(U1-PD3{slash}TIM2_CH2[ADC_ETR]-Pad40)") (class "Default")
      (node (ref "U1") (pin "40") (pinfunction "PD3/TIM2_CH2[ADC_ETR]_40") (pintype "passive"))
    )
    (net (code "62") (name "unconnected-(U1-PD4{slash}TIM2_CH1{slash}[BEEP]-Pad41)") (class "Default")
      (node (ref "U1") (pin "41") (pinfunction "PD4/TIM2_CH1/[BEEP]_41") (pintype "passive"))
    )
    (net (code "63") (name "unconnected-(U1-PD5{slash}UART3_TX-Pad42)") (class "Default")
      (node (ref "U1") (pin "42") (pinfunction "PD5/UART3_TX_42") (pintype "passive"))
    )
    (net (code "64") (name "unconnected-(U1-PE0{slash}CLK_CCO-Pad36)") (class "Default")
      (node (ref "U1") (pin "36") (pinfunction "PE0/CLK_CCO_36") (pintype "passive"))
    )
    (net (code "65") (name "unconnected-(U1-PE1{slash}I2C_SCL-Pad35)") (class "Default")
      (node (ref "U1") (pin "35") (pinfunction "PE1/I2C_SCL_35") (pintype "passive"))
    )
    (net (code "66") (name "unconnected-(U1-PE2{slash}I2C_SDA-Pad34)") (class "Default")
      (node (ref "U1") (pin "34") (pinfunction "PE2/I2C_SDA_34") (pintype "passive"))
    )
    (net (code "67") (name "unconnected-(U1-PE5{slash}SPI_NSS-Pad23)") (class "Default")
      (node (ref "U1") (pin "23") (pinfunction "PE5/SPI_NSS_23") (pintype "passive"))
    )
    (net (code "68") (name "unconnected-(U2-S-Pad8)") (class "Default")
      (node (ref "U2") (pin "8") (pinfunction "S_8") (pintype "passive"))
    )
    (net (code "69") (name "unconnected-(U2-Vref-Pad5)") (class "Default")
      (node (ref "U2") (pin "5") (pinfunction "Vref_5") (pintype "passive"))
    )
    (net (code "70") (name "unconnected-(U4-~{MR}-Pad3)") (class "Default")
      (node (ref "U4") (pin "3") (pinfunction "~{MR}_3") (pintype "input"))
    )
  )
)
